# proximitySensor.net
KiCad netlist of a schematic drawn in EAGLE
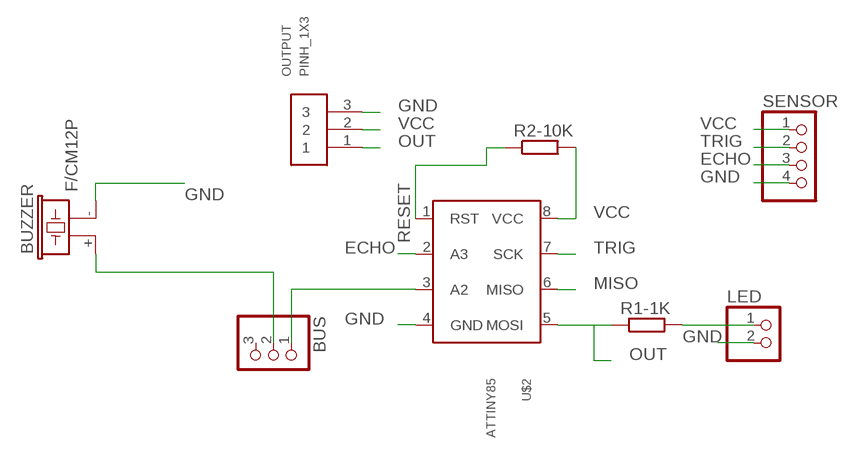
[diagram p0: schematic, sheet 1]

(export (version "E")
  (design (tool "Eeschema 10.0.6"))
  (components
    (comp (ref "BUS")
      (value "PINHD-1X3")
      (footprint "eagle-import:1X03")
      (libsource (lib "eagle-import") (part "PINHD-1X3"))
    )
    (comp (ref "BUZZER")
      (value "F/CM12P")
      (footprint "eagle-import:F_CM12P")
      (libsource (lib "eagle-import") (part "F/CM12P"))
    )
    (comp (ref "LED")
      (value "PINHD-1X2")
      (footprint "eagle-import:1X02")
      (libsource (lib "eagle-import") (part "PINHD-1X2"))
    )
    (comp (ref "OUTPUT")
      (value "PINH_1X3")
      (footprint "eagle-import:PINHEADER")
      (libsource (lib "eagle-import") (part "PINH_1X3"))
    )
    (comp (ref "R1-1K")
      (value "R-EU_0204/7")
      (footprint "eagle-import:0204_7")
      (libsource (lib "eagle-import") (part "R-EU_0204/7"))
    )
    (comp (ref "R2-10K")
      (value "R-EU_0204/7")
      (footprint "eagle-import:0204_7")
      (libsource (lib "eagle-import") (part "R-EU_0204/7"))
    )
    (comp (ref "SENSOR")
      (value "PINHD-1X4")
      (footprint "eagle-import:1X04")
      (libsource (lib "eagle-import") (part "PINHD-1X4"))
    )
    (comp (ref "U$2")
      (value "ATTINY85")
      (footprint "eagle-import:DIL-8")
      (libsource (lib "eagle-import") (part "ATTINY85"))
    )
  )
  (nets
    (net (code "1") (name "/ECHO") (class "Default")
      (node (ref "SENSOR") (pin "3") (pinfunction "3_3") (pintype "passive"))
      (node (ref "U$2") (pin "2") (pinfunction "A3_2") (pintype "bidirectional"))
    )
    (net (code "2") (name "/GND") (class "Default")
      (node (ref "BUZZER") (pin "-") (pinfunction "2_-") (pintype "passive"))
      (node (ref "LED") (pin "2") (pinfunction "2_2") (pintype "passive"))
      (node (ref "OUTPUT") (pin "3") (pinfunction "3_3") (pintype "bidirectional"))
      (node (ref "SENSOR") (pin "4") (pinfunction "4_4") (pintype "passive"))
      (node (ref "U$2") (pin "4") (pinfunction "GND_4") (pintype "bidirectional"))
    )
    (net (code "3") (name "/MISO") (class "Default")
      (node (ref "U$2") (pin "6") (pinfunction "MISO_6") (pintype "bidirectional"))
    )
    (net (code "4") (name "/OUT") (class "Default")
      (node (ref "OUTPUT") (pin "1") (pinfunction "1_1") (pintype "bidirectional"))
      (node (ref "R1-1K") (pin "1") (pinfunction "1_1") (pintype "passive"))
      (node (ref "U$2") (pin "5") (pinfunction "MOSI_5") (pintype "bidirectional"))
    )
    (net (code "5") (name "/RESET") (class "Default")
      (node (ref "R2-10K") (pin "1") (pinfunction "1_1") (pintype "passive"))
      (node (ref "U$2") (pin "1") (pinfunction "RST_1") (pintype "bidirectional"))
    )
    (net (code "6") (name "/TRIG") (class "Default")
      (node (ref "SENSOR") (pin "2") (pinfunction "2_2") (pintype "passive"))
      (node (ref "U$2") (pin "7") (pinfunction "SCK_7") (pintype "bidirectional"))
    )
    (net (code "7") (name "/VCC") (class "Default")
      (node (ref "OUTPUT") (pin "2") (pinfunction "2_2") (pintype "bidirectional"))
      (node (ref "R2-10K") (pin "2") (pinfunction "2_2") (pintype "passive"))
      (node (ref "SENSOR") (pin "1") (pinfunction "1_1") (pintype "passive"))
      (node (ref "U$2") (pin "8") (pinfunction "VCC_8") (pintype "bidirectional"))
    )
    (net (code "8") (name "Net-(BUZZER-1)") (class "Default")
      (node (ref "BUS") (pin "2") (pinfunction "2_2") (pintype "passive"))
      (node (ref "BUZZER") (pin "+") (pinfunction "1_+") (pintype "passive"))
    )
    (net (code "9") (name "Net-(LED-Pad1)") (class "Default")
      (node (ref "LED") (pin "1") (pinfunction "1_1") (pintype "passive"))
      (node (ref "R1-1K") (pin "2") (pinfunction "2_2") (pintype "passive"))
    )
    (net (code "10") (name "Net-(U$2-A2)") (class "Default")
      (node (ref "BUS") (pin "1") (pinfunction "1_1") (pintype "passive"))
      (node (ref "U$2") (pin "3") (pinfunction "A2_3") (pintype "bidirectional"))
    )
    (net (code "11") (name "unconnected-(BUS-Pad3)") (class "Default")
      (node (ref "BUS") (pin "3") (pinfunction "3_3") (pintype "passive"))
    )
  )
)
